# Power.net
KiCad netlist of a schematic drawn in Altium Designer
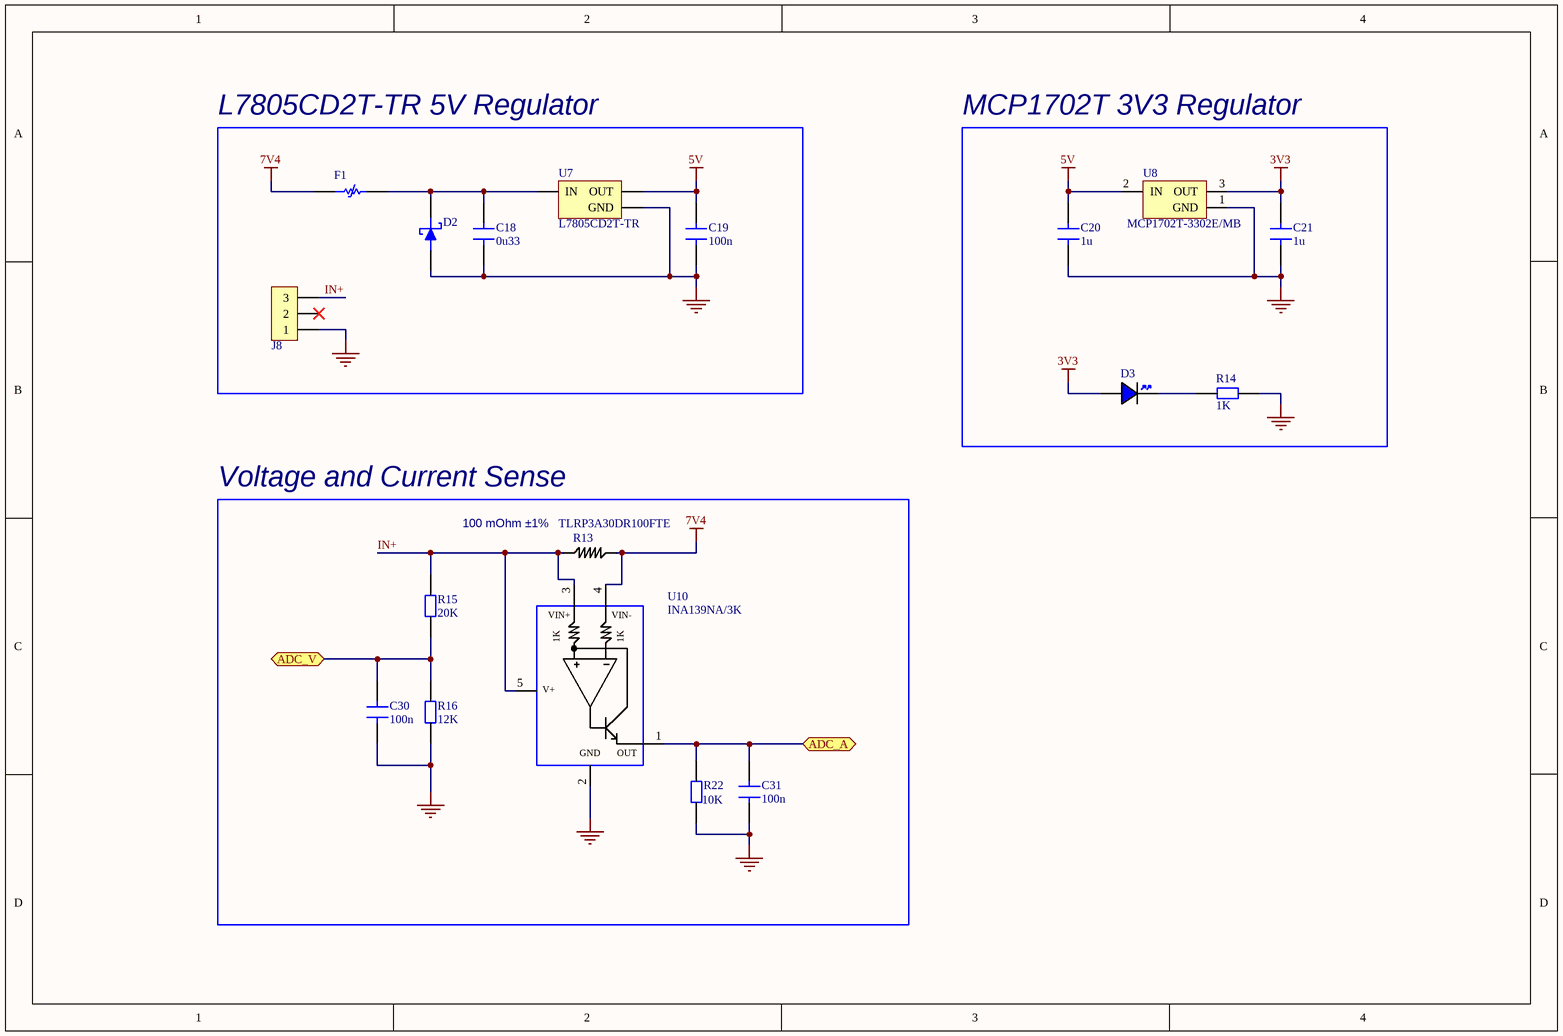
[diagram p0: Power.SchDoc]

(export (version "E")
  (design (tool "Eeschema 10.0.6"))
  (components
    (comp (ref "C18")
      (value "0u33")
      (footprint "CAP 0805")
      (description "Capacitor SMD 0805 50V")
      (libsource (lib "Schlib") (part "CAP 0805 50V"))
    )
    (comp (ref "C19")
      (value "100n")
      (footprint "CAP 0805")
      (description "Capacitor SMD 0805 50V")
      (libsource (lib "Schlib") (part "CAP 0805 50V"))
    )
    (comp (ref "C20")
      (value "1u")
      (footprint "CAP 0805")
      (description "Capacitor SMD 0805 50V")
      (libsource (lib "Schlib") (part "CAP 0805 50V"))
    )
    (comp (ref "C21")
      (value "1u")
      (footprint "CAP 0805")
      (description "Capacitor SMD 0805 50V")
      (libsource (lib "Schlib") (part "CAP 0805 50V"))
    )
    (comp (ref "C30")
      (value "100n")
      (footprint "CAP 0805")
      (description "Capacitor SMD 0805 50V")
      (libsource (lib "Schlib") (part "CAP 0805 50V"))
    )
    (comp (ref "C31")
      (value "100n")
      (footprint "CAP 0805")
      (description "Capacitor SMD 0805 50V")
      (libsource (lib "Schlib") (part "CAP 0805 50V"))
    )
    (comp (ref "D2")
      (value "SMBJ8.5CA")
      (footprint "SMBJ12CA-13-F")
      (description "Diode TVS Single Bi-Dir 8.5V 600W 2-Pin SMB")
      (fields (field (name "MANUFACTURER") "Bourns"))
      (libsource (lib "Schlib") (part "SMBJ8.5CA"))
    )
    (comp (ref "D3")
      (value "LED 0805 BLUE")
      (footprint "LED 0805 BLUE")
      (description "LED 0805 GREEN SMD")
      (libsource (lib "Schlib") (part "LED 0805 BLUE"))
    )
    (comp (ref "F1")
      (value "0ZCG0160AF2C")
      (footprint "0ZCG0075FF2C")
      (description "Ptc Reset Fuse 12V 1.6A 1812")
      (fields (field (name "MANUFACTURER") "Bel"))
      (libsource (lib "Schlib") (part "0ZCG0160AF2C"))
    )
    (comp (ref "J8")
      (value "JST B3B-XH-A")
      (footprint "JST_B3B-XH-A")
      (description "Connector Header, XH Series, 3 Position, 2.50mm, Through Hole, Press-Fit, Solder, Natural")
      (fields
        (field (name "MANUFACTURER") "JST")
        (field (name "MANUFACTURER PART NUMBER") "B3B-XH-A(LF)(SN)")
      )
      (libsource (lib "Schlib") (part "JST B3B-XH-A"))
    )
    (comp (ref "R13")
      (value "TLRP3A30DR100FTE")
      (footprint "RES 2512")
      (description "Res, 0R1, 1%, 3W, Metal Strip, SMD Rohs Compliant: Yes")
      (fields (field (name "MANUFACTURER") "TE Connectivity"))
      (libsource (lib "Schlib") (part "TLRP3A30DR100FTE"))
    )
    (comp (ref "R14")
      (value "1K")
      (footprint "RES 0603")
      (description "Resistor SMD 0603")
      (libsource (lib "Schlib") (part "RES 0603"))
    )
    (comp (ref "R15")
      (value "20K")
      (footprint "RES 0805")
      (description "Resistor SMD 0805")
      (libsource (lib "Schlib") (part "RES 0805"))
    )
    (comp (ref "R16")
      (value "12K")
      (footprint "RES 0805")
      (description "Resistor SMD 0805")
      (libsource (lib "Schlib") (part "RES 0805"))
    )
    (comp (ref "R22")
      (value "10K")
      (footprint "RES 0805")
      (description "Resistor SMD 0805")
      (libsource (lib "Schlib") (part "RES 0805"))
    )
    (comp (ref "U7")
      (value "L7805CD2T-TR")
      (footprint "L7805ABD2T-TR")
      (description "Standard Regulator Pos 5V 1.5A 3-Pin(2+Tab) D2PAK T/R / IC REG LDO 5V 1.5A D2PAK")
      (fields (field (name "MANUFACTURER") "STMicroelectronics"))
      (libsource (lib "Schlib") (part "L7805CD2T-TR"))
    )
    (comp (ref "U8")
      (value "MCP1702T-3302E/MB")
      (footprint "MCP1702T-3302E/MB")
      (description "LDO Regulator Pos 3.3V 0.25A Automotive 4-Pin(3+Tab) SOT-89 T/R")
      (fields (field (name "MANUFACTURER") "Microchip"))
      (libsource (lib "Schlib") (part "MCP1702T-3302E/MB"))
    )
    (comp (ref "U10")
      (value "INA139NA/3K")
      (footprint "INA139NA")
      (description "2.7 to 36V, 440kHz Variable gain current sense amplifier 5-SOT-23 -40 to 125")
      (fields (field (name "MANUFACTURER") "Texas Instruments"))
      (libsource (lib "Schlib") (part "INA139NA/3K"))
    )
  )
  (nets
    (net (code "1") (name "/ADC_A") (class "Default")
      (node (ref "C31") (pin "2") (pinfunction "2_2") (pintype "passive"))
      (node (ref "R22") (pin "2") (pinfunction "2_2") (pintype "passive"))
      (node (ref "U10") (pin "1") (pinfunction "OUT_1") (pintype "passive"))
    )
    (net (code "2") (name "/ADC_V") (class "Default")
      (node (ref "C30") (pin "2") (pinfunction "2_2") (pintype "passive"))
      (node (ref "R15") (pin "1") (pinfunction "1_1") (pintype "passive"))
      (node (ref "R16") (pin "2") (pinfunction "2_2") (pintype "passive"))
    )
    (net (code "3") (name "/IN+") (class "Default")
      (node (ref "J8") (pin "3") (pinfunction "3_3") (pintype "passive"))
      (node (ref "R13") (pin "2") (pinfunction "2_2") (pintype "passive"))
      (node (ref "R15") (pin "2") (pinfunction "2_2") (pintype "passive"))
      (node (ref "U10") (pin "3") (pinfunction "VIN+_3") (pintype "passive"))
      (node (ref "U10") (pin "5") (pinfunction "V+_5") (pintype "passive"))
    )
    (net (code "4") (name "3V3") (class "Default")
      (node (ref "C21") (pin "2") (pinfunction "2_2") (pintype "passive"))
      (node (ref "D3") (pin "A") (pinfunction "A_A") (pintype "passive"))
      (node (ref "U8") (pin "3") (pinfunction "OUT_3") (pintype "passive"))
    )
    (net (code "5") (name "5V") (class "Default")
      (node (ref "C19") (pin "2") (pinfunction "2_2") (pintype "passive"))
      (node (ref "C20") (pin "2") (pinfunction "2_2") (pintype "passive"))
      (node (ref "U7") (pin "3") (pinfunction "OUT_3") (pintype "passive"))
      (node (ref "U8") (pin "2") (pinfunction "IN_2") (pintype "passive"))
    )
    (net (code "6") (name "7V4") (class "Default")
      (node (ref "F1") (pin "1") (pintype "passive"))
      (node (ref "R13") (pin "1") (pinfunction "1_1") (pintype "passive"))
      (node (ref "U10") (pin "4") (pinfunction "VIN+_4") (pintype "passive"))
    )
    (net (code "7") (name "GND") (class "Default")
      (node (ref "C18") (pin "1") (pinfunction "1_1") (pintype "passive"))
      (node (ref "C19") (pin "1") (pinfunction "1_1") (pintype "passive"))
      (node (ref "C20") (pin "1") (pinfunction "1_1") (pintype "passive"))
      (node (ref "C21") (pin "1") (pinfunction "1_1") (pintype "passive"))
      (node (ref "C30") (pin "1") (pinfunction "1_1") (pintype "passive"))
      (node (ref "C31") (pin "1") (pinfunction "1_1") (pintype "passive"))
      (node (ref "D2") (pin "1") (pintype "passive"))
      (node (ref "J8") (pin "1") (pinfunction "1_1") (pintype "passive"))
      (node (ref "R14") (pin "2") (pinfunction "2_2") (pintype "passive"))
      (node (ref "R16") (pin "1") (pinfunction "1_1") (pintype "passive"))
      (node (ref "R22") (pin "1") (pinfunction "1_1") (pintype "passive"))
      (node (ref "U10") (pin "2") (pinfunction "GND_2") (pintype "passive"))
      (node (ref "U7") (pin "2") (pinfunction "GND_2") (pintype "passive"))
      (node (ref "U8") (pin "1") (pinfunction "GND_1") (pintype "passive"))
    )
    (net (code "8") (name "Net-(D3-PadK)") (class "Default")
      (node (ref "D3") (pin "K") (pinfunction "K_K") (pintype "passive"))
      (node (ref "R14") (pin "1") (pinfunction "1_1") (pintype "passive"))
    )
    (net (code "9") (name "Net-(U7-IN)") (class "Default")
      (node (ref "C18") (pin "2") (pinfunction "2_2") (pintype "passive"))
      (node (ref "D2") (pin "2") (pintype "passive"))
      (node (ref "F1") (pin "2") (pintype "passive"))
      (node (ref "U7") (pin "1") (pinfunction "IN_1") (pintype "passive"))
    )
    (net (code "10") (name "unconnected-(J8-Pad2)") (class "Default")
      (node (ref "J8") (pin "2") (pinfunction "2_2") (pintype "passive+no_connect"))
    )
  )
)
